# splitter.net
KiCad netlist of a schematic drawn in EAGLE
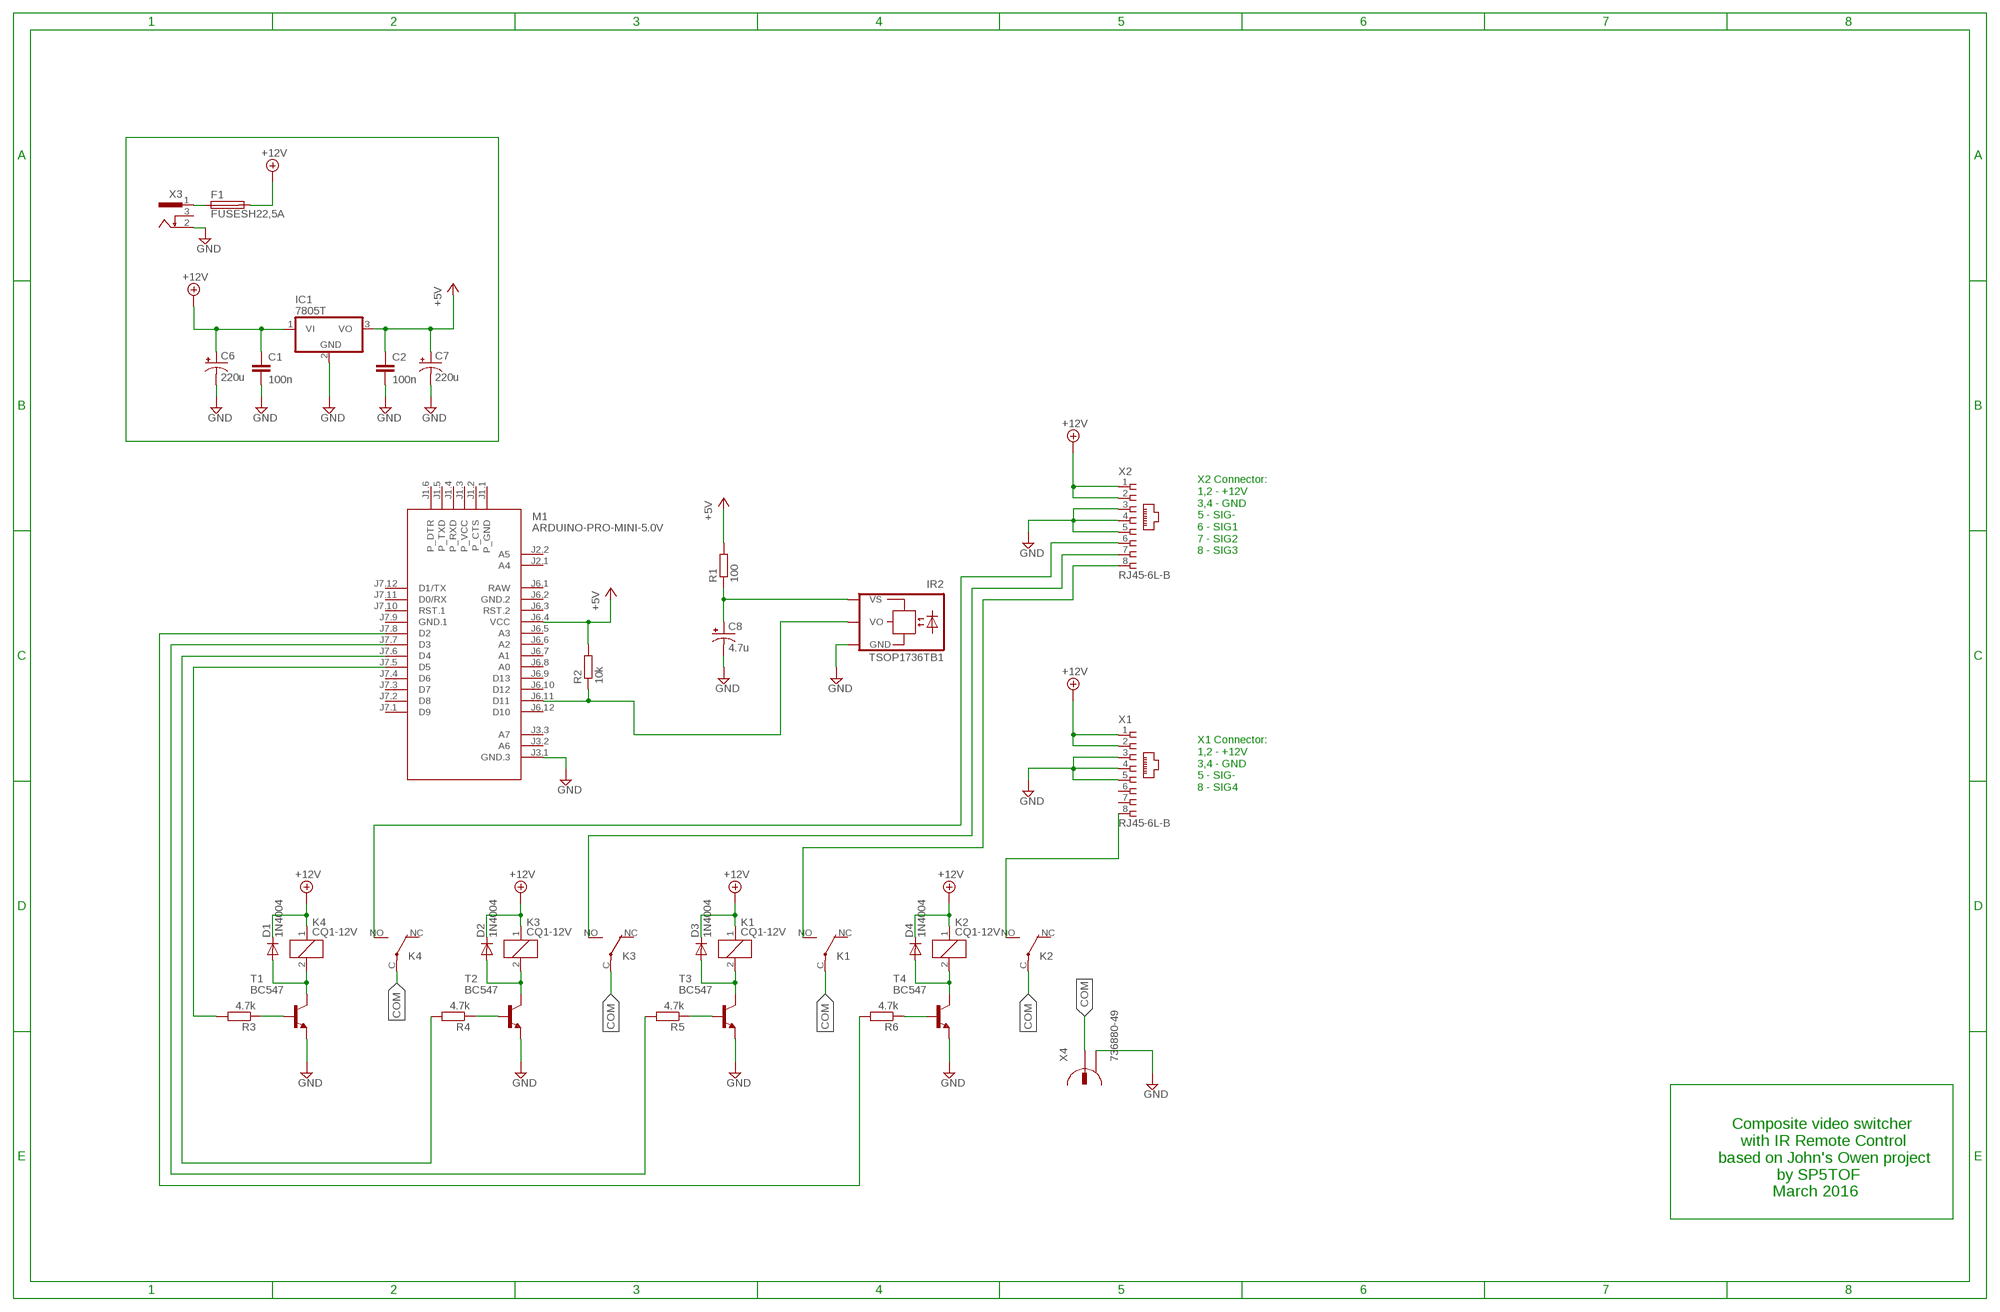
[diagram p0: schematic, sheet 1]

(export (version "E")
  (design (tool "Eeschema 10.0.6"))
  (components
    (comp (ref "C1")
      (value "100n")
      (footprint "eagle-import:C025-024X044")
      (libsource (lib "eagle-import") (part "C-EU025-024X044"))
    )
    (comp (ref "C2")
      (value "100n")
      (footprint "eagle-import:C025-024X044")
      (libsource (lib "eagle-import") (part "C-EU025-024X044"))
    )
    (comp (ref "C6")
      (value "220u")
      (footprint "eagle-import:CPOL-RADIAL-10UF-25V")
      (libsource (lib "eagle-import") (part "CAP_POLPTH2"))
    )
    (comp (ref "C7")
      (value "220u")
      (footprint "eagle-import:CPOL-RADIAL-10UF-25V")
      (libsource (lib "eagle-import") (part "CAP_POLPTH2"))
    )
    (comp (ref "C8")
      (value "4.7u")
      (footprint "eagle-import:CPOL-RADIAL-10UF-25V")
      (libsource (lib "eagle-import") (part "CAP_POLPTH2"))
    )
    (comp (ref "D1")
      (value "1N4004")
      (footprint "eagle-import:DO41-10")
      (libsource (lib "eagle-import") (part "1N4004"))
    )
    (comp (ref "D2")
      (value "1N4004")
      (footprint "eagle-import:DO41-10")
      (libsource (lib "eagle-import") (part "1N4004"))
    )
    (comp (ref "D3")
      (value "1N4004")
      (footprint "eagle-import:DO41-10")
      (libsource (lib "eagle-import") (part "1N4004"))
    )
    (comp (ref "D4")
      (value "1N4004")
      (footprint "eagle-import:DO41-10")
      (libsource (lib "eagle-import") (part "1N4004"))
    )
    (comp (ref "F1")
      (value "FUSESH22,5A")
      (footprint "eagle-import:SH22,5A")
      (libsource (lib "eagle-import") (part "FUSESH22,5A"))
    )
    (comp (ref "IC1")
      (value "7805T")
      (footprint "eagle-import:TO220H")
      (libsource (lib "eagle-import") (part "78T05"))
    )
    (comp (ref "IR2")
      (value "TSOP1736TB1")
      (footprint "eagle-import:TSOP17_TB1")
      (libsource (lib "eagle-import") (part "TSOP17TB136"))
    )
    (comp (ref "K1")
      (value "CQ1-12V")
      (footprint "eagle-import:CQ1")
      (libsource (lib "eagle-import") (part "CQ1-12V"))
    )
    (comp (ref "K2")
      (value "CQ1-12V")
      (footprint "eagle-import:CQ1")
      (libsource (lib "eagle-import") (part "CQ1-12V"))
    )
    (comp (ref "K3")
      (value "CQ1-12V")
      (footprint "eagle-import:CQ1")
      (libsource (lib "eagle-import") (part "CQ1-12V"))
    )
    (comp (ref "K4")
      (value "CQ1-12V")
      (footprint "eagle-import:CQ1")
      (libsource (lib "eagle-import") (part "CQ1-12V"))
    )
    (comp (ref "M1")
      (value "ARDUINO-PRO-MINI-5.0V")
      (footprint "eagle-import:ARDUINO-PRO-MINI")
      (libsource (lib "eagle-import") (part "ARDUINO-PRO-MINI-5.0V"))
    )
    (comp (ref "R1")
      (value "100")
      (footprint "eagle-import:0204_7")
      (libsource (lib "eagle-import") (part "R-EU_0204/7"))
    )
    (comp (ref "R2")
      (value "10k")
      (footprint "eagle-import:0204_7")
      (libsource (lib "eagle-import") (part "R-EU_0204/7"))
    )
    (comp (ref "R3")
      (value "4.7k")
      (footprint "eagle-import:0204_7")
      (libsource (lib "eagle-import") (part "R-EU_0204/7"))
    )
    (comp (ref "R4")
      (value "4.7k")
      (footprint "eagle-import:0204_7")
      (libsource (lib "eagle-import") (part "R-EU_0204/7"))
    )
    (comp (ref "R5")
      (value "4.7k")
      (footprint "eagle-import:0204_7")
      (libsource (lib "eagle-import") (part "R-EU_0204/7"))
    )
    (comp (ref "R6")
      (value "4.7k")
      (footprint "eagle-import:0204_7")
      (libsource (lib "eagle-import") (part "R-EU_0204/7"))
    )
    (comp (ref "T1")
      (value "BC547")
      (footprint "eagle-import:TO92")
      (libsource (lib "eagle-import") (part "BC547"))
    )
    (comp (ref "T2")
      (value "BC547")
      (footprint "eagle-import:TO92")
      (libsource (lib "eagle-import") (part "BC547"))
    )
    (comp (ref "T3")
      (value "BC547")
      (footprint "eagle-import:TO92")
      (libsource (lib "eagle-import") (part "BC547"))
    )
    (comp (ref "T4")
      (value "BC547")
      (footprint "eagle-import:TO92")
      (libsource (lib "eagle-import") (part "BC547"))
    )
    (comp (ref "X1")
      (value "RJ45-6L-B")
      (footprint "eagle-import:RJ45-NO-SHIELD")
      (libsource (lib "eagle-import") (part "RJ45-6L-B"))
    )
    (comp (ref "X2")
      (value "RJ45-6L-B")
      (footprint "eagle-import:RJ45-NO-SHIELD")
      (libsource (lib "eagle-import") (part "RJ45-6L-B"))
    )
    (comp (ref "X3")
      (value "733980-62")
      (footprint "eagle-import:733980-62")
      (libsource (lib "eagle-import") (part "73398?0-62"))
    )
    (comp (ref "X4")
      (value "736880-49")
      (footprint "eagle-import:736880-49")
      (libsource (lib "eagle-import") (part "736880-49"))
    )
  )
  (nets
    (net (code "1") (name "+5V") (class "Default")
      (node (ref "C2") (pin "1") (pinfunction "1_1") (pintype "passive"))
      (node (ref "C7") (pin "1") (pinfunction "+_1") (pintype "passive"))
      (node (ref "IC1") (pin "3") (pinfunction "VO_3") (pintype "passive"))
      (node (ref "M1") (pin "J6.4") (pinfunction "VCC_J6.4") (pintype "power_in"))
      (node (ref "R1") (pin "2") (pinfunction "2_2") (pintype "passive"))
      (node (ref "R2") (pin "2") (pinfunction "2_2") (pintype "passive"))
    )
    (net (code "2") (name "+12V") (class "Default")
      (node (ref "C1") (pin "1") (pinfunction "1_1") (pintype "passive"))
      (node (ref "C6") (pin "1") (pinfunction "+_1") (pintype "passive"))
      (node (ref "D1") (pin "C") (pinfunction "C_C") (pintype "passive"))
      (node (ref "D2") (pin "C") (pinfunction "C_C") (pintype "passive"))
      (node (ref "D3") (pin "C") (pinfunction "C_C") (pintype "passive"))
      (node (ref "D4") (pin "C") (pinfunction "C_C") (pintype "passive"))
      (node (ref "F1") (pin "2") (pinfunction "2_2") (pintype "passive"))
      (node (ref "IC1") (pin "1") (pinfunction "VI_1") (pintype "input"))
      (node (ref "K1") (pin "1") (pinfunction "1_1") (pintype "passive"))
      (node (ref "K2") (pin "1") (pinfunction "1_1") (pintype "passive"))
      (node (ref "K3") (pin "1") (pinfunction "1_1") (pintype "passive"))
      (node (ref "K4") (pin "1") (pinfunction "1_1") (pintype "passive"))
      (node (ref "X1") (pin "1") (pinfunction "1_1") (pintype "passive"))
      (node (ref "X1") (pin "2") (pinfunction "2_2") (pintype "passive"))
      (node (ref "X2") (pin "1") (pinfunction "1_1") (pintype "passive"))
      (node (ref "X2") (pin "2") (pinfunction "2_2") (pintype "passive"))
    )
    (net (code "3") (name "/GND.1") (class "Default")
      (node (ref "M1") (pin "J7.9") (pinfunction "GND.1_J7.9") (pintype "power_in"))
    )
    (net (code "4") (name "/GND.2") (class "Default")
      (node (ref "M1") (pin "J6.2") (pinfunction "GND.2_J6.2") (pintype "power_in"))
    )
    (net (code "5") (name "/RAW") (class "Default")
      (node (ref "M1") (pin "J6.1") (pinfunction "RAW_J6.1") (pintype "power_in"))
    )
    (net (code "6") (name "COM") (class "Default")
      (node (ref "K1") (pin "C") (pinfunction "P_C") (pintype "passive"))
      (node (ref "K2") (pin "C") (pinfunction "P_C") (pintype "passive"))
      (node (ref "K3") (pin "C") (pinfunction "P_C") (pintype "passive"))
      (node (ref "K4") (pin "C") (pinfunction "P_C") (pintype "passive"))
      (node (ref "X4") (pin "1") (pinfunction "1_1") (pintype "passive"))
    )
    (net (code "7") (name "GND") (class "Default")
      (node (ref "C1") (pin "2") (pinfunction "2_2") (pintype "passive"))
      (node (ref "C2") (pin "2") (pinfunction "2_2") (pintype "passive"))
      (node (ref "C6") (pin "2") (pinfunction "-_2") (pintype "passive"))
      (node (ref "C7") (pin "2") (pinfunction "-_2") (pintype "passive"))
      (node (ref "C8") (pin "2") (pinfunction "-_2") (pintype "passive"))
      (node (ref "IC1") (pin "2") (pinfunction "GND_2") (pintype "passive"))
      (node (ref "IR2") (pin "GND") (pinfunction "GND_GND") (pintype "power_in"))
      (node (ref "M1") (pin "J3.1") (pinfunction "GND.3_J3.1") (pintype "bidirectional"))
      (node (ref "T1") (pin "1") (pinfunction "E_1") (pintype "passive"))
      (node (ref "T2") (pin "1") (pinfunction "E_1") (pintype "passive"))
      (node (ref "T3") (pin "1") (pinfunction "E_1") (pintype "passive"))
      (node (ref "T4") (pin "1") (pinfunction "E_1") (pintype "passive"))
      (node (ref "X1") (pin "3") (pinfunction "3_3") (pintype "passive"))
      (node (ref "X1") (pin "4") (pinfunction "4_4") (pintype "passive"))
      (node (ref "X1") (pin "5") (pinfunction "5_5") (pintype "passive"))
      (node (ref "X2") (pin "3") (pinfunction "3_3") (pintype "passive"))
      (node (ref "X2") (pin "4") (pinfunction "4_4") (pintype "passive"))
      (node (ref "X2") (pin "5") (pinfunction "5_5") (pintype "passive"))
      (node (ref "X3") (pin "2") (pinfunction "2_2") (pintype "passive"))
      (node (ref "X4") (pin "2") (pinfunction "2_2") (pintype "passive"))
    )
    (net (code "8") (name "Net-(C8-+)") (class "Default")
      (node (ref "C8") (pin "1") (pinfunction "+_1") (pintype "passive"))
      (node (ref "IR2") (pin "VS") (pinfunction "VS_VS") (pintype "power_in"))
      (node (ref "R1") (pin "1") (pinfunction "1_1") (pintype "passive"))
    )
    (net (code "9") (name "Net-(F1-Pad1)") (class "Default")
      (node (ref "F1") (pin "1") (pinfunction "1_1") (pintype "passive"))
      (node (ref "X3") (pin "1") (pinfunction "1_1") (pintype "passive"))
    )
    (net (code "10") (name "Net-(K1B-S)") (class "Default")
      (node (ref "K1") (pin "NO") (pinfunction "S_NO") (pintype "passive"))
      (node (ref "X2") (pin "8") (pinfunction "8_8") (pintype "passive"))
    )
    (net (code "11") (name "Net-(K2B-S)") (class "Default")
      (node (ref "K2") (pin "NO") (pinfunction "S_NO") (pintype "passive"))
      (node (ref "X1") (pin "8") (pinfunction "8_8") (pintype "passive"))
    )
    (net (code "12") (name "Net-(K3B-S)") (class "Default")
      (node (ref "K3") (pin "NO") (pinfunction "S_NO") (pintype "passive"))
      (node (ref "X2") (pin "7") (pinfunction "7_7") (pintype "passive"))
    )
    (net (code "13") (name "Net-(K4B-S)") (class "Default")
      (node (ref "K4") (pin "NO") (pinfunction "S_NO") (pintype "passive"))
      (node (ref "X2") (pin "6") (pinfunction "6_6") (pintype "passive"))
    )
    (net (code "14") (name "Net-(M1-D2)") (class "Default")
      (node (ref "M1") (pin "J7.8") (pinfunction "D2_J7.8") (pintype "bidirectional"))
      (node (ref "R6") (pin "2") (pinfunction "2_2") (pintype "passive"))
    )
    (net (code "15") (name "Net-(M1-D3)") (class "Default")
      (node (ref "M1") (pin "J7.7") (pinfunction "D3_J7.7") (pintype "bidirectional"))
      (node (ref "R5") (pin "2") (pinfunction "2_2") (pintype "passive"))
    )
    (net (code "16") (name "Net-(M1-D4)") (class "Default")
      (node (ref "M1") (pin "J7.6") (pinfunction "D4_J7.6") (pintype "bidirectional"))
      (node (ref "R4") (pin "2") (pinfunction "2_2") (pintype "passive"))
    )
    (net (code "17") (name "Net-(M1-D5)") (class "Default")
      (node (ref "M1") (pin "J7.5") (pinfunction "D5_J7.5") (pintype "bidirectional"))
      (node (ref "R3") (pin "2") (pinfunction "2_2") (pintype "passive"))
    )
    (net (code "18") (name "Net-(M1-D11)") (class "Default")
      (node (ref "IR2") (pin "VO") (pinfunction "VO_VO") (pintype "open_collector"))
      (node (ref "M1") (pin "J6.11") (pinfunction "D11_J6.11") (pintype "bidirectional"))
      (node (ref "R2") (pin "1") (pinfunction "1_1") (pintype "passive"))
    )
    (net (code "19") (name "Net-(T1-B)") (class "Default")
      (node (ref "R3") (pin "1") (pinfunction "1_1") (pintype "passive"))
      (node (ref "T1") (pin "2") (pinfunction "B_2") (pintype "passive"))
    )
    (net (code "20") (name "Net-(T1-C)") (class "Default")
      (node (ref "D1") (pin "A") (pinfunction "A_A") (pintype "passive"))
      (node (ref "K4") (pin "2") (pinfunction "2_2") (pintype "passive"))
      (node (ref "T1") (pin "3") (pinfunction "C_3") (pintype "passive"))
    )
    (net (code "21") (name "Net-(T2-B)") (class "Default")
      (node (ref "R4") (pin "1") (pinfunction "1_1") (pintype "passive"))
      (node (ref "T2") (pin "2") (pinfunction "B_2") (pintype "passive"))
    )
    (net (code "22") (name "Net-(T2-C)") (class "Default")
      (node (ref "D2") (pin "A") (pinfunction "A_A") (pintype "passive"))
      (node (ref "K3") (pin "2") (pinfunction "2_2") (pintype "passive"))
      (node (ref "T2") (pin "3") (pinfunction "C_3") (pintype "passive"))
    )
    (net (code "23") (name "Net-(T3-B)") (class "Default")
      (node (ref "R5") (pin "1") (pinfunction "1_1") (pintype "passive"))
      (node (ref "T3") (pin "2") (pinfunction "B_2") (pintype "passive"))
    )
    (net (code "24") (name "Net-(T3-C)") (class "Default")
      (node (ref "D3") (pin "A") (pinfunction "A_A") (pintype "passive"))
      (node (ref "K1") (pin "2") (pinfunction "2_2") (pintype "passive"))
      (node (ref "T3") (pin "3") (pinfunction "C_3") (pintype "passive"))
    )
    (net (code "25") (name "Net-(T4-B)") (class "Default")
      (node (ref "R6") (pin "1") (pinfunction "1_1") (pintype "passive"))
      (node (ref "T4") (pin "2") (pinfunction "B_2") (pintype "passive"))
    )
    (net (code "26") (name "Net-(T4-C)") (class "Default")
      (node (ref "D4") (pin "A") (pinfunction "A_A") (pintype "passive"))
      (node (ref "K2") (pin "2") (pinfunction "2_2") (pintype "passive"))
      (node (ref "T4") (pin "3") (pinfunction "C_3") (pintype "passive"))
    )
    (net (code "27") (name "unconnected-(K1B-O-PadNC)") (class "Default")
      (node (ref "K1") (pin "NC") (pinfunction "O_NC") (pintype "passive"))
    )
    (net (code "28") (name "unconnected-(K2B-O-PadNC)") (class "Default")
      (node (ref "K2") (pin "NC") (pinfunction "O_NC") (pintype "passive"))
    )
    (net (code "29") (name "unconnected-(K3B-O-PadNC)") (class "Default")
      (node (ref "K3") (pin "NC") (pinfunction "O_NC") (pintype "passive"))
    )
    (net (code "30") (name "unconnected-(K4B-O-PadNC)") (class "Default")
      (node (ref "K4") (pin "NC") (pinfunction "O_NC") (pintype "passive"))
    )
    (net (code "31") (name "unconnected-(M1-A0-PadJ6.8)") (class "Default")
      (node (ref "M1") (pin "J6.8") (pinfunction "A0_J6.8") (pintype "bidirectional"))
    )
    (net (code "32") (name "unconnected-(M1-A1-PadJ6.7)") (class "Default")
      (node (ref "M1") (pin "J6.7") (pinfunction "A1_J6.7") (pintype "bidirectional"))
    )
    (net (code "33") (name "unconnected-(M1-A2-PadJ6.6)") (class "Default")
      (node (ref "M1") (pin "J6.6") (pinfunction "A2_J6.6") (pintype "bidirectional"))
    )
    (net (code "34") (name "unconnected-(M1-A3-PadJ6.5)") (class "Default")
      (node (ref "M1") (pin "J6.5") (pinfunction "A3_J6.5") (pintype "bidirectional"))
    )
    (net (code "35") (name "unconnected-(M1-A4-PadJ2.1)") (class "Default")
      (node (ref "M1") (pin "J2.1") (pinfunction "A4_J2.1") (pintype "bidirectional"))
    )
    (net (code "36") (name "unconnected-(M1-A5-PadJ2.2)") (class "Default")
      (node (ref "M1") (pin "J2.2") (pinfunction "A5_J2.2") (pintype "bidirectional"))
    )
    (net (code "37") (name "unconnected-(M1-A6-PadJ3.2)") (class "Default")
      (node (ref "M1") (pin "J3.2") (pinfunction "A6_J3.2") (pintype "bidirectional"))
    )
    (net (code "38") (name "unconnected-(M1-A7-PadJ3.3)") (class "Default")
      (node (ref "M1") (pin "J3.3") (pinfunction "A7_J3.3") (pintype "bidirectional"))
    )
    (net (code "39") (name "unconnected-(M1-D0{slash}RX-PadJ7.11)") (class "Default")
      (node (ref "M1") (pin "J7.11") (pinfunction "D0/RX_J7.11") (pintype "bidirectional"))
    )
    (net (code "40") (name "unconnected-(M1-D1{slash}TX-PadJ7.12)") (class "Default")
      (node (ref "M1") (pin "J7.12") (pinfunction "D1/TX_J7.12") (pintype "bidirectional"))
    )
    (net (code "41") (name "unconnected-(M1-D6-PadJ7.4)") (class "Default")
      (node (ref "M1") (pin "J7.4") (pinfunction "D6_J7.4") (pintype "bidirectional"))
    )
    (net (code "42") (name "unconnected-(M1-D7-PadJ7.3)") (class "Default")
      (node (ref "M1") (pin "J7.3") (pinfunction "D7_J7.3") (pintype "bidirectional"))
    )
    (net (code "43") (name "unconnected-(M1-D8-PadJ7.2)") (class "Default")
      (node (ref "M1") (pin "J7.2") (pinfunction "D8_J7.2") (pintype "bidirectional"))
    )
    (net (code "44") (name "unconnected-(M1-D9-PadJ7.1)") (class "Default")
      (node (ref "M1") (pin "J7.1") (pinfunction "D9_J7.1") (pintype "bidirectional"))
    )
    (net (code "45") (name "unconnected-(M1-D10-PadJ6.12)") (class "Default")
      (node (ref "M1") (pin "J6.12") (pinfunction "D10_J6.12") (pintype "bidirectional"))
    )
    (net (code "46") (name "unconnected-(M1-D12-PadJ6.10)") (class "Default")
      (node (ref "M1") (pin "J6.10") (pinfunction "D12_J6.10") (pintype "bidirectional"))
    )
    (net (code "47") (name "unconnected-(M1-D13-PadJ6.9)") (class "Default")
      (node (ref "M1") (pin "J6.9") (pinfunction "D13_J6.9") (pintype "bidirectional"))
    )
    (net (code "48") (name "unconnected-(M1-P_CTS-PadJ1.2)") (class "Default")
      (node (ref "M1") (pin "J1.2") (pinfunction "P_CTS_J1.2") (pintype "bidirectional"))
    )
    (net (code "49") (name "unconnected-(M1-P_DTR-PadJ1.6)") (class "Default")
      (node (ref "M1") (pin "J1.6") (pinfunction "P_DTR_J1.6") (pintype "bidirectional"))
    )
    (net (code "50") (name "unconnected-(M1-P_GND-PadJ1.1)") (class "Default")
      (node (ref "M1") (pin "J1.1") (pinfunction "P_GND_J1.1") (pintype "bidirectional"))
    )
    (net (code "51") (name "unconnected-(M1-P_RXD-PadJ1.4)") (class "Default")
      (node (ref "M1") (pin "J1.4") (pinfunction "P_RXD_J1.4") (pintype "bidirectional"))
    )
    (net (code "52") (name "unconnected-(M1-P_TXD-PadJ1.5)") (class "Default")
      (node (ref "M1") (pin "J1.5") (pinfunction "P_TXD_J1.5") (pintype "bidirectional"))
    )
    (net (code "53") (name "unconnected-(M1-P_VCC-PadJ1.3)") (class "Default")
      (node (ref "M1") (pin "J1.3") (pinfunction "P_VCC_J1.3") (pintype "bidirectional"))
    )
    (net (code "54") (name "unconnected-(M1-RST.1-PadJ7.10)") (class "Default")
      (node (ref "M1") (pin "J7.10") (pinfunction "RST.1_J7.10") (pintype "bidirectional"))
    )
    (net (code "55") (name "unconnected-(M1-RST.2-PadJ6.3)") (class "Default")
      (node (ref "M1") (pin "J6.3") (pinfunction "RST.2_J6.3") (pintype "bidirectional"))
    )
    (net (code "56") (name "unconnected-(X1-Pad6)") (class "Default")
      (node (ref "X1") (pin "6") (pinfunction "6_6") (pintype "passive"))
    )
    (net (code "57") (name "unconnected-(X1-Pad7)") (class "Default")
      (node (ref "X1") (pin "7") (pinfunction "7_7") (pintype "passive"))
    )
    (net (code "58") (name "unconnected-(X3-Pad3)") (class "Default")
      (node (ref "X3") (pin "3") (pinfunction "3_3") (pintype "passive"))
    )
    (net (code "59") (name "unconnected-(X4-2-Pad2@2)") (class "Default")
      (node (ref "X4") (pin "2@2") (pinfunction "2_2@2") (pintype "passive"))
    )
  )
)
